# mainboardv0_2_2.net
KiCad netlist of a schematic drawn in EAGLE
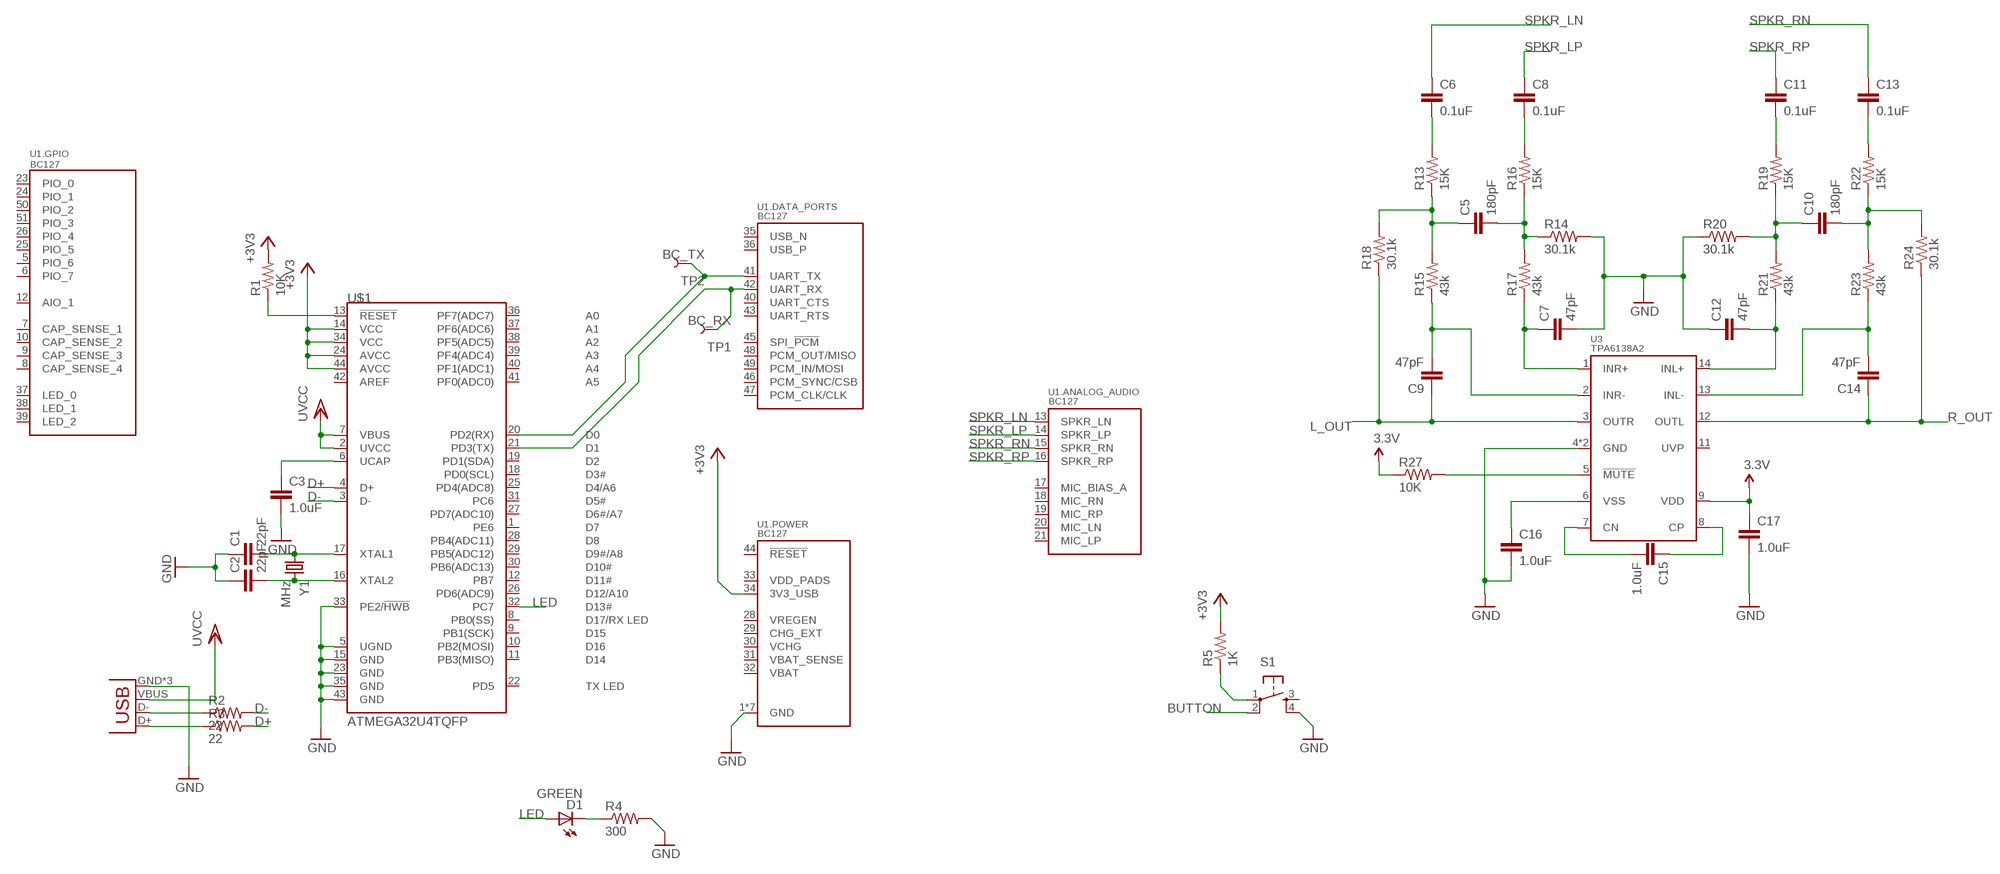
[diagram p0: schematic, sheet 1]

(export (version "E")
  (design (tool "Eeschema 10.0.6"))
  (components
    (comp (ref "C1")
      (value "22pF")
      (footprint "eagle-import:0603-CAP")
      (libsource (lib "eagle-import") (part "22PF-50V-5%(0603)"))
    )
    (comp (ref "C2")
      (value "22pF")
      (footprint "eagle-import:0603-CAP")
      (libsource (lib "eagle-import") (part "22PF-50V-5%(0603)"))
    )
    (comp (ref "C3")
      (value "1.0uF")
      (footprint "eagle-import:0603-CAP")
      (libsource (lib "eagle-import") (part "1.0UF-16V-10%(0603)"))
    )
    (comp (ref "C5")
      (value "180pF")
      (footprint "eagle-import:0603-CAP")
      (libsource (lib "eagle-import") (part "CAP0603-CAP"))
    )
    (comp (ref "C6")
      (value "0.1uF")
      (footprint "eagle-import:0603-CAP")
      (libsource (lib "eagle-import") (part "0.1UF-25V-5%(0603)"))
    )
    (comp (ref "C7")
      (value "47pF")
      (footprint "eagle-import:0603-CAP")
      (libsource (lib "eagle-import") (part "47PF-50V-5%(0603)"))
    )
    (comp (ref "C8")
      (value "0.1uF")
      (footprint "eagle-import:0603-CAP")
      (libsource (lib "eagle-import") (part "0.1UF-25V-5%(0603)"))
    )
    (comp (ref "C9")
      (value "47pF")
      (footprint "eagle-import:0603-CAP")
      (libsource (lib "eagle-import") (part "47PF-50V-5%(0603)"))
    )
    (comp (ref "C10")
      (value "180pF")
      (footprint "eagle-import:0603-CAP")
      (libsource (lib "eagle-import") (part "CAP0603-CAP"))
    )
    (comp (ref "C11")
      (value "0.1uF")
      (footprint "eagle-import:0603-CAP")
      (libsource (lib "eagle-import") (part "0.1UF-25V-5%(0603)"))
    )
    (comp (ref "C12")
      (value "47pF")
      (footprint "eagle-import:0603-CAP")
      (libsource (lib "eagle-import") (part "47PF-50V-5%(0603)"))
    )
    (comp (ref "C13")
      (value "0.1uF")
      (footprint "eagle-import:0603-CAP")
      (libsource (lib "eagle-import") (part "0.1UF-25V-5%(0603)"))
    )
    (comp (ref "C14")
      (value "47pF")
      (footprint "eagle-import:0603-CAP")
      (libsource (lib "eagle-import") (part "47PF-50V-5%(0603)"))
    )
    (comp (ref "C15")
      (value "1.0uF")
      (footprint "eagle-import:0603-CAP")
      (libsource (lib "eagle-import") (part "1.0UF-16V-10%(0603)"))
    )
    (comp (ref "C16")
      (value "1.0uF")
      (footprint "eagle-import:0603-CAP")
      (libsource (lib "eagle-import") (part "1.0UF-16V-10%(0603)"))
    )
    (comp (ref "C17")
      (value "1.0uF")
      (footprint "eagle-import:0603-CAP")
      (libsource (lib "eagle-import") (part "1.0UF-16V-10%(0603)"))
    )
    (comp (ref "D1")
      (value "GREEN")
      (footprint "eagle-import:LED-1206")
      (libsource (lib "eagle-import") (part "LED-GREENLARGE"))
    )
    (comp (ref "JP1")
      (value "USB-MICROB")
      (footprint "eagle-import:USB-MICROB")
      (libsource (lib "eagle-import") (part "USB-MICROB"))
    )
    (comp (ref "R1")
      (value "10K")
      (footprint "eagle-import:0603-RES")
      (libsource (lib "eagle-import") (part "10KOHM1/10W1%(0603)0603"))
    )
    (comp (ref "R2")
      (value "22")
      (footprint "eagle-import:0603-RES")
      (libsource (lib "eagle-import") (part "22OHM1/10W1%(0603)"))
    )
    (comp (ref "R3")
      (value "22")
      (footprint "eagle-import:0603-RES")
      (libsource (lib "eagle-import") (part "22OHM1/10W1%(0603)"))
    )
    (comp (ref "R4")
      (value "300")
      (footprint "eagle-import:0603-RES")
      (libsource (lib "eagle-import") (part "300OHM-1/10W-1%(0603)"))
    )
    (comp (ref "R5")
      (value "1K")
      (footprint "eagle-import:0603-RES")
      (libsource (lib "eagle-import") (part "1KOHM1/10W1%(0603)"))
    )
    (comp (ref "R13")
      (value "15K")
      (footprint "eagle-import:0603-RES")
      (libsource (lib "eagle-import") (part "15KOHM1/10W1%(0603)0603"))
    )
    (comp (ref "R14")
      (value "30.1k")
      (footprint "eagle-import:0603-RES")
      (libsource (lib "eagle-import") (part "30.1KOHM1/10W1%(0603)"))
    )
    (comp (ref "R15")
      (value "43k")
      (footprint "eagle-import:0603-RES")
      (libsource (lib "eagle-import") (part "43KOHM1/10W1%(0603)"))
    )
    (comp (ref "R16")
      (value "15K")
      (footprint "eagle-import:0603-RES")
      (libsource (lib "eagle-import") (part "15KOHM1/10W1%(0603)0603"))
    )
    (comp (ref "R17")
      (value "43k")
      (footprint "eagle-import:0603-RES")
      (libsource (lib "eagle-import") (part "43KOHM1/10W1%(0603)"))
    )
    (comp (ref "R18")
      (value "30.1k")
      (footprint "eagle-import:0603-RES")
      (libsource (lib "eagle-import") (part "30.1KOHM1/10W1%(0603)"))
    )
    (comp (ref "R19")
      (value "15K")
      (footprint "eagle-import:0603-RES")
      (libsource (lib "eagle-import") (part "15KOHM1/10W1%(0603)0603"))
    )
    (comp (ref "R20")
      (value "30.1k")
      (footprint "eagle-import:0603-RES")
      (libsource (lib "eagle-import") (part "30.1KOHM1/10W1%(0603)"))
    )
    (comp (ref "R21")
      (value "43k")
      (footprint "eagle-import:0603-RES")
      (libsource (lib "eagle-import") (part "43KOHM1/10W1%(0603)"))
    )
    (comp (ref "R22")
      (value "15K")
      (footprint "eagle-import:0603-RES")
      (libsource (lib "eagle-import") (part "15KOHM1/10W1%(0603)0603"))
    )
    (comp (ref "R23")
      (value "43k")
      (footprint "eagle-import:0603-RES")
      (libsource (lib "eagle-import") (part "43KOHM1/10W1%(0603)"))
    )
    (comp (ref "R24")
      (value "30.1k")
      (footprint "eagle-import:0603-RES")
      (libsource (lib "eagle-import") (part "30.1KOHM1/10W1%(0603)"))
    )
    (comp (ref "R27")
      (value "10K")
      (footprint "eagle-import:0603-RES")
      (libsource (lib "eagle-import") (part "10KOHM1/10W1%(0603)0603"))
    )
    (comp (ref "S1")
      (value "TAC_SWITCHSMD")
      (footprint "eagle-import:TACTILE_SWITCH_SMD")
      (libsource (lib "eagle-import") (part "TAC_SWITCHSMD"))
    )
    (comp (ref "TP1")
      (value "BC_RX")
      (footprint "eagle-import:PAD.02X.02")
      (libsource (lib "eagle-import") (part "TEST-POINT2"))
    )
    (comp (ref "TP2")
      (value "BC_TX")
      (footprint "eagle-import:PAD.02X.02")
      (libsource (lib "eagle-import") (part "TEST-POINT2"))
    )
    (comp (ref "U$1")
      (value "ATMEGA32U4TQFP")
      (footprint "eagle-import:SPARKFUN-DIGITALIC_TQFP44")
      (libsource (lib "eagle-import") (part "ATMEGA32U4TQFP"))
    )
    (comp (ref "U1")
      (value "BC127")
      (footprint "eagle-import:BC127")
      (libsource (lib "eagle-import") (part "BC127"))
    )
    (comp (ref "U3")
      (value "TPA6138A2")
      (footprint "eagle-import:TSSOP-14")
      (libsource (lib "eagle-import") (part "TPA6138A2"))
    )
    (comp (ref "Y1")
      (value "MHz")
      (footprint "eagle-import:CRYSTAL-SMD-5X3")
      (libsource (lib "eagle-import") (part "CRYSTAL5X3"))
    )
  )
  (nets
    (net (code "1") (name "+3V3") (class "Default")
      (node (ref "R1") (pin "2") (pinfunction "2_2") (pintype "passive"))
      (node (ref "R5") (pin "2") (pinfunction "2_2") (pintype "passive"))
      (node (ref "U$1") (pin "14") (pinfunction "VCC_14") (pintype "bidirectional"))
      (node (ref "U$1") (pin "24") (pinfunction "AVCC_24") (pintype "bidirectional"))
      (node (ref "U$1") (pin "34") (pinfunction "VCC_34") (pintype "bidirectional"))
      (node (ref "U$1") (pin "44") (pinfunction "AVCC_44") (pintype "bidirectional"))
      (node (ref "U1") (pin "34") (pinfunction "3V3_USB_34") (pintype "bidirectional"))
    )
    (net (code "2") (name "/BUTTON") (class "Default")
      (node (ref "S1") (pin "2") (pinfunction "2_2") (pintype "passive"))
    )
    (net (code "3") (name "/D+") (class "Default")
      (node (ref "R3") (pin "2") (pinfunction "2_2") (pintype "passive"))
      (node (ref "U$1") (pin "4") (pinfunction "D+_4") (pintype "bidirectional"))
    )
    (net (code "4") (name "/D-") (class "Default")
      (node (ref "R2") (pin "2") (pinfunction "2_2") (pintype "passive"))
      (node (ref "U$1") (pin "3") (pinfunction "D-_3") (pintype "bidirectional"))
    )
    (net (code "5") (name "/LED") (class "Default")
      (node (ref "D1") (pin "A") (pinfunction "A_A") (pintype "passive"))
      (node (ref "U$1") (pin "32") (pinfunction "PC7_32") (pintype "bidirectional"))
    )
    (net (code "6") (name "/L_OUT") (class "Default")
      (node (ref "C9") (pin "1") (pinfunction "1_1") (pintype "passive"))
      (node (ref "R18") (pin "1") (pinfunction "1_1") (pintype "passive"))
      (node (ref "U3") (pin "3") (pinfunction "OUTR_3") (pintype "bidirectional"))
    )
    (net (code "7") (name "/R_OUT") (class "Default")
      (node (ref "C14") (pin "1") (pinfunction "1_1") (pintype "passive"))
      (node (ref "R24") (pin "1") (pinfunction "1_1") (pintype "passive"))
      (node (ref "U3") (pin "12") (pinfunction "OUTL_12") (pintype "bidirectional"))
    )
    (net (code "8") (name "/SPKR_LN") (class "Default")
      (node (ref "C6") (pin "1") (pinfunction "1_1") (pintype "passive"))
      (node (ref "U1") (pin "13") (pinfunction "SPKR_LN_13") (pintype "bidirectional"))
    )
    (net (code "9") (name "/SPKR_LP") (class "Default")
      (node (ref "C8") (pin "1") (pinfunction "1_1") (pintype "passive"))
      (node (ref "U1") (pin "14") (pinfunction "SPKR_LP_14") (pintype "bidirectional"))
    )
    (net (code "10") (name "/SPKR_RN") (class "Default")
      (node (ref "C13") (pin "1") (pinfunction "1_1") (pintype "passive"))
      (node (ref "U1") (pin "15") (pinfunction "SPKR_RN_15") (pintype "bidirectional"))
    )
    (net (code "11") (name "/SPKR_RP") (class "Default")
      (node (ref "C11") (pin "1") (pinfunction "1_1") (pintype "passive"))
      (node (ref "U1") (pin "16") (pinfunction "SPKR_RP_16") (pintype "bidirectional"))
    )
    (net (code "12") (name "3.3V") (class "Default")
      (node (ref "C17") (pin "1") (pinfunction "1_1") (pintype "passive"))
      (node (ref "R27") (pin "1") (pinfunction "1_1") (pintype "passive"))
      (node (ref "U3") (pin "9") (pinfunction "VDD_9") (pintype "bidirectional"))
    )
    (net (code "13") (name "GND") (class "Default")
      (node (ref "C1") (pin "1") (pinfunction "1_1") (pintype "passive"))
      (node (ref "C12") (pin "1") (pinfunction "1_1") (pintype "passive"))
      (node (ref "C16") (pin "2") (pinfunction "2_2") (pintype "passive"))
      (node (ref "C17") (pin "2") (pinfunction "2_2") (pintype "passive"))
      (node (ref "C2") (pin "1") (pinfunction "1_1") (pintype "passive"))
      (node (ref "C3") (pin "2") (pinfunction "2_2") (pintype "passive"))
      (node (ref "C7") (pin "2") (pinfunction "2_2") (pintype "passive"))
      (node (ref "JP1") (pin "GND") (pinfunction "GND_GND") (pintype "bidirectional"))
      (node (ref "JP1") (pin "MT1") (pinfunction "GND_MT1") (pintype "bidirectional"))
      (node (ref "JP1") (pin "MT2") (pinfunction "GND_MT2") (pintype "bidirectional"))
      (node (ref "R14") (pin "2") (pinfunction "2_2") (pintype "passive"))
      (node (ref "R20") (pin "1") (pinfunction "1_1") (pintype "passive"))
      (node (ref "R4") (pin "2") (pinfunction "2_2") (pintype "passive"))
      (node (ref "S1") (pin "4") (pinfunction "4_4") (pintype "passive"))
      (node (ref "U$1") (pin "15") (pinfunction "GND_15") (pintype "bidirectional"))
      (node (ref "U$1") (pin "23") (pinfunction "GND_23") (pintype "bidirectional"))
      (node (ref "U$1") (pin "33") (pinfunction "PE2/~{HWB}_33") (pintype "bidirectional"))
      (node (ref "U$1") (pin "35") (pinfunction "GND_35") (pintype "bidirectional"))
      (node (ref "U$1") (pin "43") (pinfunction "GND_43") (pintype "bidirectional"))
      (node (ref "U$1") (pin "5") (pinfunction "UGND_5") (pintype "bidirectional"))
      (node (ref "U1") (pin "1") (pinfunction "GND_1") (pintype "bidirectional"))
      (node (ref "U1") (pin "11") (pinfunction "GND_11") (pintype "bidirectional"))
      (node (ref "U1") (pin "2") (pinfunction "GND_2") (pintype "bidirectional"))
      (node (ref "U1") (pin "22") (pinfunction "GND_22") (pintype "bidirectional"))
      (node (ref "U1") (pin "27") (pinfunction "GND_27") (pintype "bidirectional"))
      (node (ref "U1") (pin "3") (pinfunction "GND_3") (pintype "bidirectional"))
      (node (ref "U1") (pin "4") (pinfunction "GND_4") (pintype "bidirectional"))
      (node (ref "U3") (pin "10") (pinfunction "GND_10") (pintype "bidirectional"))
      (node (ref "U3") (pin "4") (pinfunction "GND_4") (pintype "bidirectional"))
    )
    (net (code "14") (name "Net-(C5-Pad1)") (class "Default")
      (node (ref "C5") (pin "1") (pinfunction "1_1") (pintype "passive"))
      (node (ref "R13") (pin "1") (pinfunction "1_1") (pintype "passive"))
      (node (ref "R15") (pin "2") (pinfunction "2_2") (pintype "passive"))
      (node (ref "R18") (pin "2") (pinfunction "2_2") (pintype "passive"))
    )
    (net (code "15") (name "Net-(C5-Pad2)") (class "Default")
      (node (ref "C5") (pin "2") (pinfunction "2_2") (pintype "passive"))
      (node (ref "R14") (pin "1") (pinfunction "1_1") (pintype "passive"))
      (node (ref "R16") (pin "1") (pinfunction "1_1") (pintype "passive"))
      (node (ref "R17") (pin "2") (pinfunction "2_2") (pintype "passive"))
    )
    (net (code "16") (name "Net-(C6-Pad2)") (class "Default")
      (node (ref "C6") (pin "2") (pinfunction "2_2") (pintype "passive"))
      (node (ref "R13") (pin "2") (pinfunction "2_2") (pintype "passive"))
    )
    (net (code "17") (name "Net-(C8-Pad2)") (class "Default")
      (node (ref "C8") (pin "2") (pinfunction "2_2") (pintype "passive"))
      (node (ref "R16") (pin "2") (pinfunction "2_2") (pintype "passive"))
    )
    (net (code "18") (name "Net-(C10-Pad1)") (class "Default")
      (node (ref "C10") (pin "1") (pinfunction "1_1") (pintype "passive"))
      (node (ref "R19") (pin "1") (pinfunction "1_1") (pintype "passive"))
      (node (ref "R20") (pin "2") (pinfunction "2_2") (pintype "passive"))
      (node (ref "R21") (pin "2") (pinfunction "2_2") (pintype "passive"))
    )
    (net (code "19") (name "Net-(C10-Pad2)") (class "Default")
      (node (ref "C10") (pin "2") (pinfunction "2_2") (pintype "passive"))
      (node (ref "R22") (pin "1") (pinfunction "1_1") (pintype "passive"))
      (node (ref "R23") (pin "2") (pinfunction "2_2") (pintype "passive"))
      (node (ref "R24") (pin "2") (pinfunction "2_2") (pintype "passive"))
    )
    (net (code "20") (name "Net-(C11-Pad2)") (class "Default")
      (node (ref "C11") (pin "2") (pinfunction "2_2") (pintype "passive"))
      (node (ref "R19") (pin "2") (pinfunction "2_2") (pintype "passive"))
    )
    (net (code "21") (name "Net-(C13-Pad2)") (class "Default")
      (node (ref "C13") (pin "2") (pinfunction "2_2") (pintype "passive"))
      (node (ref "R22") (pin "2") (pinfunction "2_2") (pintype "passive"))
    )
    (net (code "22") (name "Net-(D1-PadC)") (class "Default")
      (node (ref "D1") (pin "C") (pinfunction "C_C") (pintype "passive"))
      (node (ref "R4") (pin "1") (pinfunction "1_1") (pintype "passive"))
    )
    (net (code "23") (name "Net-(JP1-PadD+)") (class "Default")
      (node (ref "JP1") (pin "D+") (pinfunction "D+_D+") (pintype "bidirectional"))
      (node (ref "R3") (pin "1") (pinfunction "1_1") (pintype "passive"))
    )
    (net (code "24") (name "Net-(JP1-PadD-)") (class "Default")
      (node (ref "JP1") (pin "D-") (pinfunction "D-_D-") (pintype "bidirectional"))
      (node (ref "R2") (pin "1") (pinfunction "1_1") (pintype "passive"))
    )
    (net (code "25") (name "Net-(R5-Pad1)") (class "Default")
      (node (ref "R5") (pin "1") (pinfunction "1_1") (pintype "passive"))
      (node (ref "S1") (pin "1") (pinfunction "1_1") (pintype "passive"))
    )
    (net (code "26") (name "Net-(TP1-1)") (class "Default")
      (node (ref "TP1") (pin "P$1") (pinfunction "1_P$1") (pintype "bidirectional"))
      (node (ref "U$1") (pin "21") (pinfunction "PD3(TX)_21") (pintype "bidirectional"))
      (node (ref "U1") (pin "42") (pinfunction "UART_RX_42") (pintype "bidirectional"))
    )
    (net (code "27") (name "Net-(TP2-1)") (class "Default")
      (node (ref "TP2") (pin "P$1") (pinfunction "1_P$1") (pintype "bidirectional"))
      (node (ref "U$1") (pin "20") (pinfunction "PD2(RX)_20") (pintype "bidirectional"))
      (node (ref "U1") (pin "41") (pinfunction "UART_TX_41") (pintype "bidirectional"))
    )
    (net (code "28") (name "Net-(U$1-UCAP)") (class "Default")
      (node (ref "C3") (pin "1") (pinfunction "1_1") (pintype "passive"))
      (node (ref "U$1") (pin "6") (pinfunction "UCAP_6") (pintype "bidirectional"))
    )
    (net (code "29") (name "Net-(U$1-XTAL1)") (class "Default")
      (node (ref "C1") (pin "2") (pinfunction "2_2") (pintype "passive"))
      (node (ref "U$1") (pin "17") (pinfunction "XTAL1_17") (pintype "bidirectional"))
      (node (ref "Y1") (pin "1") (pinfunction "1_1") (pintype "passive"))
    )
    (net (code "30") (name "Net-(U$1-XTAL2)") (class "Default")
      (node (ref "C2") (pin "2") (pinfunction "2_2") (pintype "passive"))
      (node (ref "U$1") (pin "16") (pinfunction "XTAL2_16") (pintype "bidirectional"))
      (node (ref "Y1") (pin "3") (pinfunction "2_3") (pintype "passive"))
    )
    (net (code "31") (name "Net-(U$1-~{RESET})") (class "Default")
      (node (ref "R1") (pin "1") (pinfunction "1_1") (pintype "passive"))
      (node (ref "U$1") (pin "13") (pinfunction "~{RESET}_13") (pintype "bidirectional"))
    )
    (net (code "32") (name "Net-(U3-CN)") (class "Default")
      (node (ref "C15") (pin "2") (pinfunction "2_2") (pintype "passive"))
      (node (ref "U3") (pin "7") (pinfunction "CN_7") (pintype "bidirectional"))
    )
    (net (code "33") (name "Net-(U3-CP)") (class "Default")
      (node (ref "C15") (pin "1") (pinfunction "1_1") (pintype "passive"))
      (node (ref "U3") (pin "8") (pinfunction "CP_8") (pintype "bidirectional"))
    )
    (net (code "34") (name "Net-(U3-INL+)") (class "Default")
      (node (ref "C12") (pin "2") (pinfunction "2_2") (pintype "passive"))
      (node (ref "R21") (pin "1") (pinfunction "1_1") (pintype "passive"))
      (node (ref "U3") (pin "14") (pinfunction "INL+_14") (pintype "bidirectional"))
    )
    (net (code "35") (name "Net-(U3-INL-)") (class "Default")
      (node (ref "C14") (pin "2") (pinfunction "2_2") (pintype "passive"))
      (node (ref "R23") (pin "1") (pinfunction "1_1") (pintype "passive"))
      (node (ref "U3") (pin "13") (pinfunction "INL-_13") (pintype "bidirectional"))
    )
    (net (code "36") (name "Net-(U3-INR+)") (class "Default")
      (node (ref "C7") (pin "1") (pinfunction "1_1") (pintype "passive"))
      (node (ref "R17") (pin "1") (pinfunction "1_1") (pintype "passive"))
      (node (ref "U3") (pin "1") (pinfunction "INR+_1") (pintype "bidirectional"))
    )
    (net (code "37") (name "Net-(U3-INR-)") (class "Default")
      (node (ref "C9") (pin "2") (pinfunction "2_2") (pintype "passive"))
      (node (ref "R15") (pin "1") (pinfunction "1_1") (pintype "passive"))
      (node (ref "U3") (pin "2") (pinfunction "INR-_2") (pintype "bidirectional"))
    )
    (net (code "38") (name "Net-(U3-VSS)") (class "Default")
      (node (ref "C16") (pin "1") (pinfunction "1_1") (pintype "passive"))
      (node (ref "U3") (pin "6") (pinfunction "VSS_6") (pintype "bidirectional"))
    )
    (net (code "39") (name "Net-(U3-~{MUTE})") (class "Default")
      (node (ref "R27") (pin "2") (pinfunction "2_2") (pintype "passive"))
      (node (ref "U3") (pin "5") (pinfunction "~{MUTE}_5") (pintype "bidirectional"))
    )
    (net (code "40") (name "UVCC") (class "Default")
      (node (ref "JP1") (pin "VBUS") (pinfunction "VBUS_VBUS") (pintype "bidirectional"))
      (node (ref "U$1") (pin "2") (pinfunction "UVCC_2") (pintype "bidirectional"))
      (node (ref "U$1") (pin "7") (pinfunction "VBUS_7") (pintype "bidirectional"))
    )
    (net (code "41") (name "unconnected-(S1-Pad3)") (class "Default")
      (node (ref "S1") (pin "3") (pinfunction "3_3") (pintype "passive"))
    )
    (net (code "42") (name "unconnected-(U$1-AREF-Pad42)") (class "Default")
      (node (ref "U$1") (pin "42") (pinfunction "AREF_42") (pintype "bidirectional"))
    )
    (net (code "43") (name "unconnected-(U$1-PB0(SS)-Pad8)") (class "Default")
      (node (ref "U$1") (pin "8") (pinfunction "PB0(SS)_8") (pintype "bidirectional"))
    )
    (net (code "44") (name "unconnected-(U$1-PB1(SCK)-Pad9)") (class "Default")
      (node (ref "U$1") (pin "9") (pinfunction "PB1(SCK)_9") (pintype "bidirectional"))
    )
    (net (code "45") (name "unconnected-(U$1-PB2(MOSI)-Pad10)") (class "Default")
      (node (ref "U$1") (pin "10") (pinfunction "PB2(MOSI)_10") (pintype "bidirectional"))
    )
    (net (code "46") (name "unconnected-(U$1-PB3(MISO)-Pad11)") (class "Default")
      (node (ref "U$1") (pin "11") (pinfunction "PB3(MISO)_11") (pintype "bidirectional"))
    )
    (net (code "47") (name "unconnected-(U$1-PB4(ADC11)-Pad28)") (class "Default")
      (node (ref "U$1") (pin "28") (pinfunction "PB4(ADC11)_28") (pintype "bidirectional"))
    )
    (net (code "48") (name "unconnected-(U$1-PB5(ADC12)-Pad29)") (class "Default")
      (node (ref "U$1") (pin "29") (pinfunction "PB5(ADC12)_29") (pintype "bidirectional"))
    )
    (net (code "49") (name "unconnected-(U$1-PB6(ADC13)-Pad30)") (class "Default")
      (node (ref "U$1") (pin "30") (pinfunction "PB6(ADC13)_30") (pintype "bidirectional"))
    )
    (net (code "50") (name "unconnected-(U$1-PB7-Pad12)") (class "Default")
      (node (ref "U$1") (pin "12") (pinfunction "PB7_12") (pintype "bidirectional"))
    )
    (net (code "51") (name "unconnected-(U$1-PC6-Pad31)") (class "Default")
      (node (ref "U$1") (pin "31") (pinfunction "PC6_31") (pintype "bidirectional"))
    )
    (net (code "52") (name "unconnected-(U$1-PD0(SCL)-Pad18)") (class "Default")
      (node (ref "U$1") (pin "18") (pinfunction "PD0(SCL)_18") (pintype "bidirectional"))
    )
    (net (code "53") (name "unconnected-(U$1-PD1(SDA)-Pad19)") (class "Default")
      (node (ref "U$1") (pin "19") (pinfunction "PD1(SDA)_19") (pintype "bidirectional"))
    )
    (net (code "54") (name "unconnected-(U$1-PD4(ADC8)-Pad25)") (class "Default")
      (node (ref "U$1") (pin "25") (pinfunction "PD4(ADC8)_25") (pintype "bidirectional"))
    )
    (net (code "55") (name "unconnected-(U$1-PD5-Pad22)") (class "Default")
      (node (ref "U$1") (pin "22") (pinfunction "PD5_22") (pintype "bidirectional"))
    )
    (net (code "56") (name "unconnected-(U$1-PD6(ADC9)-Pad26)") (class "Default")
      (node (ref "U$1") (pin "26") (pinfunction "PD6(ADC9)_26") (pintype "bidirectional"))
    )
    (net (code "57") (name "unconnected-(U$1-PD7(ADC10)-Pad27)") (class "Default")
      (node (ref "U$1") (pin "27") (pinfunction "PD7(ADC10)_27") (pintype "bidirectional"))
    )
    (net (code "58") (name "unconnected-(U$1-PE6-Pad1)") (class "Default")
      (node (ref "U$1") (pin "1") (pinfunction "PE6_1") (pintype "bidirectional"))
    )
    (net (code "59") (name "unconnected-(U$1-PF0(ADC0)-Pad41)") (class "Default")
      (node (ref "U$1") (pin "41") (pinfunction "PF0(ADC0)_41") (pintype "bidirectional"))
    )
    (net (code "60") (name "unconnected-(U$1-PF1(ADC1)-Pad40)") (class "Default")
      (node (ref "U$1") (pin "40") (pinfunction "PF1(ADC1)_40") (pintype "bidirectional"))
    )
    (net (code "61") (name "unconnected-(U$1-PF4(ADC4)-Pad39)") (class "Default")
      (node (ref "U$1") (pin "39") (pinfunction "PF4(ADC4)_39") (pintype "bidirectional"))
    )
    (net (code "62") (name "unconnected-(U$1-PF5(ADC5)-Pad38)") (class "Default")
      (node (ref "U$1") (pin "38") (pinfunction "PF5(ADC5)_38") (pintype "bidirectional"))
    )
    (net (code "63") (name "unconnected-(U$1-PF6(ADC6)-Pad37)") (class "Default")
      (node (ref "U$1") (pin "37") (pinfunction "PF6(ADC6)_37") (pintype "bidirectional"))
    )
    (net (code "64") (name "unconnected-(U$1-PF7(ADC7)-Pad36)") (class "Default")
      (node (ref "U$1") (pin "36") (pinfunction "PF7(ADC7)_36") (pintype "bidirectional"))
    )
    (net (code "65") (name "unconnected-(U1A-MIC_BIAS_A-Pad17)") (class "Default")
      (node (ref "U1") (pin "17") (pinfunction "MIC_BIAS_A_17") (pintype "bidirectional"))
    )
    (net (code "66") (name "unconnected-(U1A-MIC_LN-Pad20)") (class "Default")
      (node (ref "U1") (pin "20") (pinfunction "MIC_LN_20") (pintype "bidirectional"))
    )
    (net (code "67") (name "unconnected-(U1A-MIC_LP-Pad21)") (class "Default")
      (node (ref "U1") (pin "21") (pinfunction "MIC_LP_21") (pintype "bidirectional"))
    )
    (net (code "68") (name "unconnected-(U1A-MIC_RN-Pad18)") (class "Default")
      (node (ref "U1") (pin "18") (pinfunction "MIC_RN_18") (pintype "bidirectional"))
    )
    (net (code "69") (name "unconnected-(U1A-MIC_RP-Pad19)") (class "Default")
      (node (ref "U1") (pin "19") (pinfunction "MIC_RP_19") (pintype "bidirectional"))
    )
    (net (code "70") (name "unconnected-(U1B-PCM_CLK{slash}CLK-Pad47)") (class "Default")
      (node (ref "U1") (pin "47") (pinfunction "PCM_CLK/CLK_47") (pintype "bidirectional"))
    )
    (net (code "71") (name "unconnected-(U1B-PCM_IN{slash}MOSI-Pad49)") (class "Default")
      (node (ref "U1") (pin "49") (pinfunction "PCM_IN/MOSI_49") (pintype "bidirectional"))
    )
    (net (code "72") (name "unconnected-(U1B-PCM_OUT{slash}MISO-Pad48)") (class "Default")
      (node (ref "U1") (pin "48") (pinfunction "PCM_OUT/MISO_48") (pintype "bidirectional"))
    )
    (net (code "73") (name "unconnected-(U1B-PCM_SYNC{slash}CSB-Pad46)") (class "Default")
      (node (ref "U1") (pin "46") (pinfunction "PCM_SYNC/CSB_46") (pintype "bidirectional"))
    )
    (net (code "74") (name "unconnected-(U1B-SPI_~{PCM}-Pad45)") (class "Default")
      (node (ref "U1") (pin "45") (pinfunction "SPI_~{PCM}_45") (pintype "bidirectional"))
    )
    (net (code "75") (name "unconnected-(U1B-UART_CTS-Pad40)") (class "Default")
      (node (ref "U1") (pin "40") (pinfunction "UART_CTS_40") (pintype "bidirectional"))
    )
    (net (code "76") (name "unconnected-(U1B-UART_RTS-Pad43)") (class "Default")
      (node (ref "U1") (pin "43") (pinfunction "UART_RTS_43") (pintype "bidirectional"))
    )
    (net (code "77") (name "unconnected-(U1B-USB_N-Pad35)") (class "Default")
      (node (ref "U1") (pin "35") (pinfunction "USB_N_35") (pintype "bidirectional"))
    )
    (net (code "78") (name "unconnected-(U1B-USB_P-Pad36)") (class "Default")
      (node (ref "U1") (pin "36") (pinfunction "USB_P_36") (pintype "bidirectional"))
    )
    (net (code "79") (name "unconnected-(U1C-AIO_1-Pad12)") (class "Default")
      (node (ref "U1") (pin "12") (pinfunction "AIO_1_12") (pintype "bidirectional"))
    )
    (net (code "80") (name "unconnected-(U1C-CAP_SENSE_1-Pad7)") (class "Default")
      (node (ref "U1") (pin "7") (pinfunction "CAP_SENSE_1_7") (pintype "bidirectional"))
    )
    (net (code "81") (name "unconnected-(U1C-CAP_SENSE_2-Pad10)") (class "Default")
      (node (ref "U1") (pin "10") (pinfunction "CAP_SENSE_2_10") (pintype "bidirectional"))
    )
    (net (code "82") (name "unconnected-(U1C-CAP_SENSE_3-Pad9)") (class "Default")
      (node (ref "U1") (pin "9") (pinfunction "CAP_SENSE_3_9") (pintype "bidirectional"))
    )
    (net (code "83") (name "unconnected-(U1C-CAP_SENSE_4-Pad8)") (class "Default")
      (node (ref "U1") (pin "8") (pinfunction "CAP_SENSE_4_8") (pintype "bidirectional"))
    )
    (net (code "84") (name "unconnected-(U1C-LED_0-Pad37)") (class "Default")
      (node (ref "U1") (pin "37") (pinfunction "LED_0_37") (pintype "bidirectional"))
    )
    (net (code "85") (name "unconnected-(U1C-LED_1-Pad38)") (class "Default")
      (node (ref "U1") (pin "38") (pinfunction "LED_1_38") (pintype "bidirectional"))
    )
    (net (code "86") (name "unconnected-(U1C-LED_2-Pad39)") (class "Default")
      (node (ref "U1") (pin "39") (pinfunction "LED_2_39") (pintype "bidirectional"))
    )
    (net (code "87") (name "unconnected-(U1C-PIO_0-Pad23)") (class "Default")
      (node (ref "U1") (pin "23") (pinfunction "PIO_0_23") (pintype "bidirectional"))
    )
    (net (code "88") (name "unconnected-(U1C-PIO_1-Pad24)") (class "Default")
      (node (ref "U1") (pin "24") (pinfunction "PIO_1_24") (pintype "bidirectional"))
    )
    (net (code "89") (name "unconnected-(U1C-PIO_2-Pad50)") (class "Default")
      (node (ref "U1") (pin "50") (pinfunction "PIO_2_50") (pintype "bidirectional"))
    )
    (net (code "90") (name "unconnected-(U1C-PIO_3-Pad51)") (class "Default")
      (node (ref "U1") (pin "51") (pinfunction "PIO_3_51") (pintype "bidirectional"))
    )
    (net (code "91") (name "unconnected-(U1C-PIO_4-Pad26)") (class "Default")
      (node (ref "U1") (pin "26") (pinfunction "PIO_4_26") (pintype "bidirectional"))
    )
    (net (code "92") (name "unconnected-(U1C-PIO_5-Pad25)") (class "Default")
      (node (ref "U1") (pin "25") (pinfunction "PIO_5_25") (pintype "bidirectional"))
    )
    (net (code "93") (name "unconnected-(U1C-PIO_6-Pad5)") (class "Default")
      (node (ref "U1") (pin "5") (pinfunction "PIO_6_5") (pintype "bidirectional"))
    )
    (net (code "94") (name "unconnected-(U1C-PIO_7-Pad6)") (class "Default")
      (node (ref "U1") (pin "6") (pinfunction "PIO_7_6") (pintype "bidirectional"))
    )
    (net (code "95") (name "unconnected-(U1D-CHG_EXT-Pad29)") (class "Default")
      (node (ref "U1") (pin "29") (pinfunction "CHG_EXT_29") (pintype "bidirectional"))
    )
    (net (code "96") (name "unconnected-(U1D-VBAT-Pad32)") (class "Default")
      (node (ref "U1") (pin "32") (pinfunction "VBAT_32") (pintype "bidirectional"))
    )
    (net (code "97") (name "unconnected-(U1D-VBAT_SENSE-Pad31)") (class "Default")
      (node (ref "U1") (pin "31") (pinfunction "VBAT_SENSE_31") (pintype "bidirectional"))
    )
    (net (code "98") (name "unconnected-(U1D-VCHG-Pad30)") (class "Default")
      (node (ref "U1") (pin "30") (pinfunction "VCHG_30") (pintype "bidirectional"))
    )
    (net (code "99") (name "unconnected-(U1D-VDD_PADS-Pad33)") (class "Default")
      (node (ref "U1") (pin "33") (pinfunction "VDD_PADS_33") (pintype "bidirectional"))
    )
    (net (code "100") (name "unconnected-(U1D-VREGEN-Pad28)") (class "Default")
      (node (ref "U1") (pin "28") (pinfunction "VREGEN_28") (pintype "bidirectional"))
    )
    (net (code "101") (name "unconnected-(U1D-~{RESET}-Pad44)") (class "Default")
      (node (ref "U1") (pin "44") (pinfunction "~{RESET}_44") (pintype "bidirectional"))
    )
    (net (code "102") (name "unconnected-(U3-UVP-Pad11)") (class "Default")
      (node (ref "U3") (pin "11") (pinfunction "UVP_11") (pintype "bidirectional"))
    )
  )
)
